# smartPowerStrip.net
KiCad netlist of a schematic drawn in EAGLE
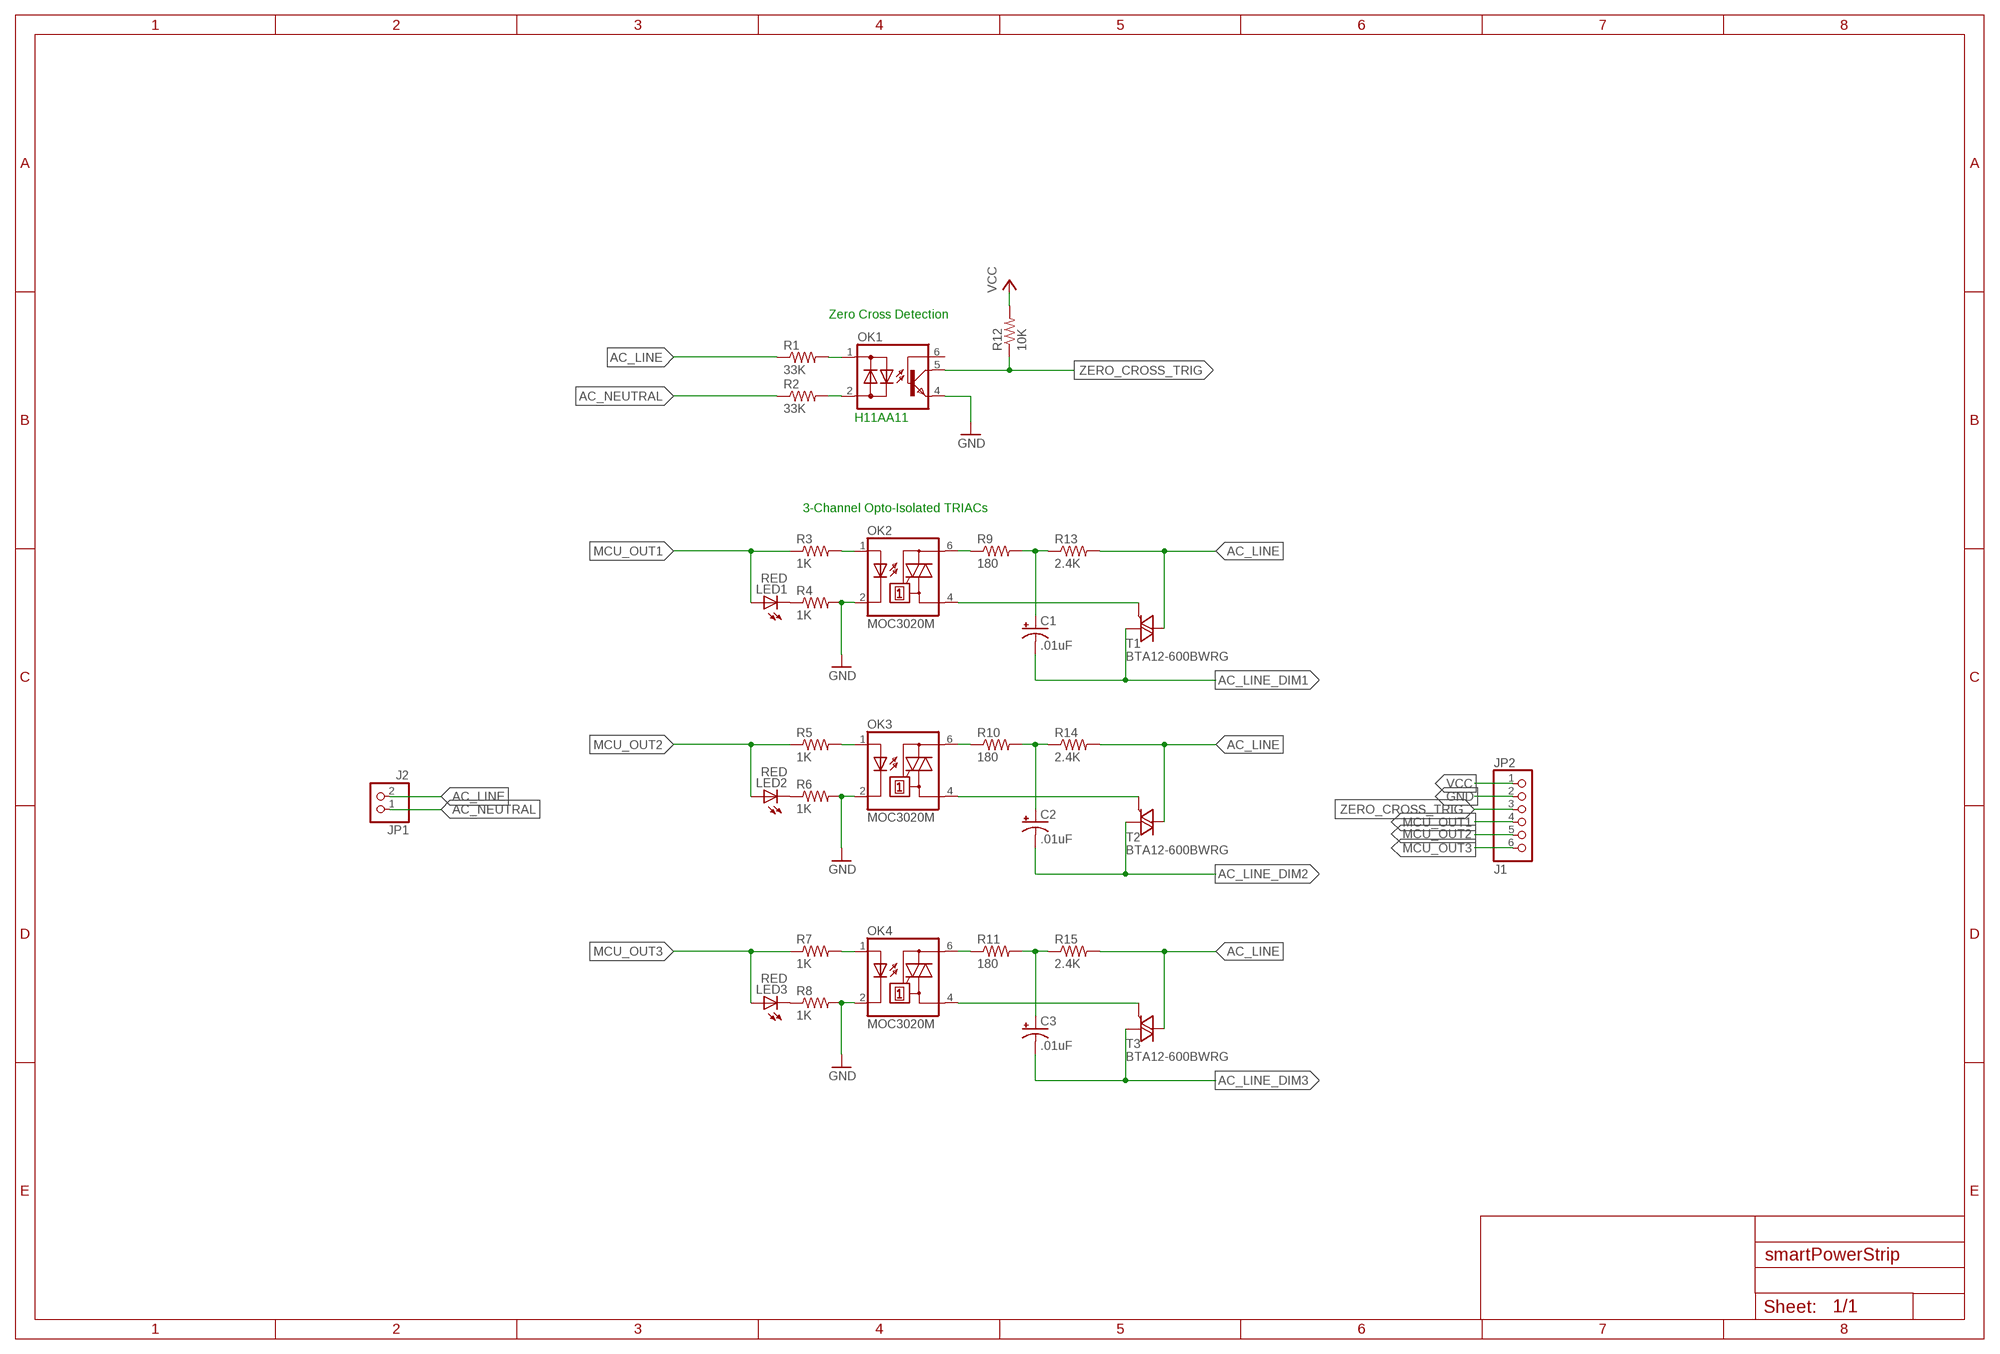
[diagram p0: schematic, sheet 1]

(export (version "E")
  (design (tool "Eeschema 10.0.6"))
  (components
    (comp (ref "C1")
      (value ".01uF")
      (footprint "eagle-import:TT2D5")
      (libsource (lib "eagle-import") (part "CPOL-USTT2D5"))
    )
    (comp (ref "C2")
      (value ".01uF")
      (footprint "eagle-import:TT2D5")
      (libsource (lib "eagle-import") (part "CPOL-USTT2D5"))
    )
    (comp (ref "C3")
      (value ".01uF")
      (footprint "eagle-import:TT2D5")
      (libsource (lib "eagle-import") (part "CPOL-USTT2D5"))
    )
    (comp (ref "JP1")
      (value "J2")
      (footprint "eagle-import:1X02")
      (libsource (lib "eagle-import") (part "PINHD-1X2"))
    )
    (comp (ref "JP2")
      (value "J1")
      (footprint "eagle-import:1X06")
      (libsource (lib "eagle-import") (part "PINHD-1X6"))
    )
    (comp (ref "LED1")
      (value "RED")
      (footprint "eagle-import:SFH480")
      (libsource (lib "eagle-import") (part "LEDSFH480"))
    )
    (comp (ref "LED2")
      (value "RED")
      (footprint "eagle-import:SFH480")
      (libsource (lib "eagle-import") (part "LEDSFH480"))
    )
    (comp (ref "LED3")
      (value "RED")
      (footprint "eagle-import:SFH480")
      (libsource (lib "eagle-import") (part "LEDSFH480"))
    )
    (comp (ref "OK1")
      (value "IL250")
      (footprint "eagle-import:DIL06")
      (fields (field (name "MF") "VISHAY/TELEFUNKEN"))
      (libsource (lib "eagle-import") (part "IL250"))
    )
    (comp (ref "OK2")
      (value "MOC3020M")
      (footprint "eagle-import:DIL06")
      (fields (field (name "MF") "FAIRCHILD SEMICONDUCTOR") (field (name "MPN") "MOC3020-M"))
      (libsource (lib "eagle-import") (part "MOC30M20"))
    )
    (comp (ref "OK3")
      (value "MOC3020M")
      (footprint "eagle-import:DIL06")
      (fields (field (name "MF") "FAIRCHILD SEMICONDUCTOR") (field (name "MPN") "MOC3020-M"))
      (libsource (lib "eagle-import") (part "MOC30M20"))
    )
    (comp (ref "OK4")
      (value "MOC3020M")
      (footprint "eagle-import:DIL06")
      (fields (field (name "MF") "FAIRCHILD SEMICONDUCTOR") (field (name "MPN") "MOC3020-M"))
      (libsource (lib "eagle-import") (part "MOC30M20"))
    )
    (comp (ref "R1")
      (value "33K")
      (footprint "eagle-import:0207_10")
      (libsource (lib "eagle-import") (part "R-US_0207/10"))
    )
    (comp (ref "R2")
      (value "33K")
      (footprint "eagle-import:0207_10")
      (libsource (lib "eagle-import") (part "R-US_0207/10"))
    )
    (comp (ref "R3")
      (value "1K")
      (footprint "eagle-import:0309V")
      (libsource (lib "eagle-import") (part "R-US_0309/V"))
    )
    (comp (ref "R4")
      (value "1K")
      (footprint "eagle-import:0309V")
      (libsource (lib "eagle-import") (part "R-US_0309/V"))
    )
    (comp (ref "R5")
      (value "1K")
      (footprint "eagle-import:0309V")
      (libsource (lib "eagle-import") (part "R-US_0309/V"))
    )
    (comp (ref "R6")
      (value "1K")
      (footprint "eagle-import:0309V")
      (libsource (lib "eagle-import") (part "R-US_0309/V"))
    )
    (comp (ref "R7")
      (value "1K")
      (footprint "eagle-import:0309V")
      (libsource (lib "eagle-import") (part "R-US_0309/V"))
    )
    (comp (ref "R8")
      (value "1K")
      (footprint "eagle-import:0309V")
      (libsource (lib "eagle-import") (part "R-US_0309/V"))
    )
    (comp (ref "R9")
      (value "180")
      (footprint "eagle-import:0309V")
      (libsource (lib "eagle-import") (part "R-US_0309/V"))
    )
    (comp (ref "R10")
      (value "180")
      (footprint "eagle-import:0309V")
      (libsource (lib "eagle-import") (part "R-US_0309/V"))
    )
    (comp (ref "R11")
      (value "180")
      (footprint "eagle-import:0309V")
      (libsource (lib "eagle-import") (part "R-US_0309/V"))
    )
    (comp (ref "R12")
      (value "10K")
      (footprint "eagle-import:0207_10")
      (libsource (lib "eagle-import") (part "R-US_0207/10"))
    )
    (comp (ref "R13")
      (value "2.4K")
      (footprint "eagle-import:0309V")
      (libsource (lib "eagle-import") (part "R-US_0309/V"))
    )
    (comp (ref "R14")
      (value "2.4K")
      (footprint "eagle-import:0309V")
      (libsource (lib "eagle-import") (part "R-US_0309/V"))
    )
    (comp (ref "R15")
      (value "2.4K")
      (footprint "eagle-import:0309V")
      (libsource (lib "eagle-import") (part "R-US_0309/V"))
    )
    (comp (ref "T1")
      (value "BTA12-600BWRG")
      (footprint "eagle-import:TO220BV")
      (libsource (lib "eagle-import") (part "BT138-V"))
    )
    (comp (ref "T2")
      (value "BTA12-600BWRG")
      (footprint "eagle-import:TO220BV")
      (libsource (lib "eagle-import") (part "BT138-V"))
    )
    (comp (ref "T3")
      (value "BTA12-600BWRG")
      (footprint "eagle-import:TO220BV")
      (libsource (lib "eagle-import") (part "BT138-V"))
    )
  )
  (nets
    (net (code "1") (name "AC_LINE") (class "Default")
      (node (ref "JP1") (pin "2") (pinfunction "2_2") (pintype "passive"))
      (node (ref "R1") (pin "1") (pinfunction "1_1") (pintype "passive"))
      (node (ref "R13") (pin "2") (pinfunction "2_2") (pintype "passive"))
      (node (ref "R14") (pin "2") (pinfunction "2_2") (pintype "passive"))
      (node (ref "R15") (pin "2") (pinfunction "2_2") (pintype "passive"))
      (node (ref "T1") (pin "T2") (pinfunction "A2_T2") (pintype "passive"))
      (node (ref "T2") (pin "T2") (pinfunction "A2_T2") (pintype "passive"))
      (node (ref "T3") (pin "T2") (pinfunction "A2_T2") (pintype "passive"))
    )
    (net (code "2") (name "AC_LINE_DIM1") (class "Default")
      (node (ref "C1") (pin "-") (pinfunction "-_-") (pintype "passive"))
      (node (ref "T1") (pin "T1") (pinfunction "A1_T1") (pintype "passive"))
    )
    (net (code "3") (name "AC_LINE_DIM2") (class "Default")
      (node (ref "C2") (pin "-") (pinfunction "-_-") (pintype "passive"))
      (node (ref "T2") (pin "T1") (pinfunction "A1_T1") (pintype "passive"))
    )
    (net (code "4") (name "AC_LINE_DIM3") (class "Default")
      (node (ref "C3") (pin "-") (pinfunction "-_-") (pintype "passive"))
      (node (ref "T3") (pin "T1") (pinfunction "A1_T1") (pintype "passive"))
    )
    (net (code "5") (name "AC_NEUTRAL") (class "Default")
      (node (ref "JP1") (pin "1") (pinfunction "1_1") (pintype "passive"))
      (node (ref "R2") (pin "1") (pinfunction "1_1") (pintype "passive"))
    )
    (net (code "6") (name "GND") (class "Default")
      (node (ref "JP2") (pin "2") (pinfunction "2_2") (pintype "passive"))
      (node (ref "OK1") (pin "4") (pinfunction "E_4") (pintype "passive"))
      (node (ref "OK2") (pin "2") (pinfunction "C_2") (pintype "passive"))
      (node (ref "OK3") (pin "2") (pinfunction "C_2") (pintype "passive"))
      (node (ref "OK4") (pin "2") (pinfunction "C_2") (pintype "passive"))
      (node (ref "R4") (pin "2") (pinfunction "2_2") (pintype "passive"))
      (node (ref "R6") (pin "2") (pinfunction "2_2") (pintype "passive"))
      (node (ref "R8") (pin "2") (pinfunction "2_2") (pintype "passive"))
    )
    (net (code "7") (name "MCU_OUT1") (class "Default")
      (node (ref "JP2") (pin "4") (pinfunction "4_4") (pintype "passive"))
      (node (ref "LED1") (pin "A") (pinfunction "A_A") (pintype "passive"))
      (node (ref "R3") (pin "1") (pinfunction "1_1") (pintype "passive"))
    )
    (net (code "8") (name "MCU_OUT2") (class "Default")
      (node (ref "JP2") (pin "5") (pinfunction "5_5") (pintype "passive"))
      (node (ref "LED2") (pin "A") (pinfunction "A_A") (pintype "passive"))
      (node (ref "R5") (pin "1") (pinfunction "1_1") (pintype "passive"))
    )
    (net (code "9") (name "MCU_OUT3") (class "Default")
      (node (ref "JP2") (pin "6") (pinfunction "6_6") (pintype "passive"))
      (node (ref "LED3") (pin "A") (pinfunction "A_A") (pintype "passive"))
      (node (ref "R7") (pin "1") (pinfunction "1_1") (pintype "passive"))
    )
    (net (code "10") (name "Net-(C1-Pad+)") (class "Default")
      (node (ref "C1") (pin "+") (pinfunction "+_+") (pintype "passive"))
      (node (ref "R13") (pin "1") (pinfunction "1_1") (pintype "passive"))
      (node (ref "R9") (pin "2") (pinfunction "2_2") (pintype "passive"))
    )
    (net (code "11") (name "Net-(C2-Pad+)") (class "Default")
      (node (ref "C2") (pin "+") (pinfunction "+_+") (pintype "passive"))
      (node (ref "R10") (pin "2") (pinfunction "2_2") (pintype "passive"))
      (node (ref "R14") (pin "1") (pinfunction "1_1") (pintype "passive"))
    )
    (net (code "12") (name "Net-(C3-Pad+)") (class "Default")
      (node (ref "C3") (pin "+") (pinfunction "+_+") (pintype "passive"))
      (node (ref "R11") (pin "2") (pinfunction "2_2") (pintype "passive"))
      (node (ref "R15") (pin "1") (pinfunction "1_1") (pintype "passive"))
    )
    (net (code "13") (name "Net-(LED1-C)") (class "Default")
      (node (ref "LED1") (pin "K") (pinfunction "C_K") (pintype "passive"))
      (node (ref "R4") (pin "1") (pinfunction "1_1") (pintype "passive"))
    )
    (net (code "14") (name "Net-(LED2-C)") (class "Default")
      (node (ref "LED2") (pin "K") (pinfunction "C_K") (pintype "passive"))
      (node (ref "R6") (pin "1") (pinfunction "1_1") (pintype "passive"))
    )
    (net (code "15") (name "Net-(LED3-C)") (class "Default")
      (node (ref "LED3") (pin "K") (pinfunction "C_K") (pintype "passive"))
      (node (ref "R8") (pin "1") (pinfunction "1_1") (pintype "passive"))
    )
    (net (code "16") (name "Net-(OK1-AC1)") (class "Default")
      (node (ref "OK1") (pin "1") (pinfunction "AC1_1") (pintype "passive"))
      (node (ref "R1") (pin "2") (pinfunction "2_2") (pintype "passive"))
    )
    (net (code "17") (name "Net-(OK1-AC2)") (class "Default")
      (node (ref "OK1") (pin "2") (pinfunction "AC2_2") (pintype "passive"))
      (node (ref "R2") (pin "2") (pinfunction "2_2") (pintype "passive"))
    )
    (net (code "18") (name "Net-(OK2-A)") (class "Default")
      (node (ref "OK2") (pin "1") (pinfunction "A_1") (pintype "passive"))
      (node (ref "R3") (pin "2") (pinfunction "2_2") (pintype "passive"))
    )
    (net (code "19") (name "Net-(OK2-A1)") (class "Default")
      (node (ref "OK2") (pin "4") (pinfunction "A1_4") (pintype "passive"))
      (node (ref "T1") (pin "G") (pinfunction "G_G") (pintype "passive"))
    )
    (net (code "20") (name "Net-(OK2-A2)") (class "Default")
      (node (ref "OK2") (pin "6") (pinfunction "A2_6") (pintype "passive"))
      (node (ref "R9") (pin "1") (pinfunction "1_1") (pintype "passive"))
    )
    (net (code "21") (name "Net-(OK3-A)") (class "Default")
      (node (ref "OK3") (pin "1") (pinfunction "A_1") (pintype "passive"))
      (node (ref "R5") (pin "2") (pinfunction "2_2") (pintype "passive"))
    )
    (net (code "22") (name "Net-(OK3-A1)") (class "Default")
      (node (ref "OK3") (pin "4") (pinfunction "A1_4") (pintype "passive"))
      (node (ref "T2") (pin "G") (pinfunction "G_G") (pintype "passive"))
    )
    (net (code "23") (name "Net-(OK3-A2)") (class "Default")
      (node (ref "OK3") (pin "6") (pinfunction "A2_6") (pintype "passive"))
      (node (ref "R10") (pin "1") (pinfunction "1_1") (pintype "passive"))
    )
    (net (code "24") (name "Net-(OK4-A)") (class "Default")
      (node (ref "OK4") (pin "1") (pinfunction "A_1") (pintype "passive"))
      (node (ref "R7") (pin "2") (pinfunction "2_2") (pintype "passive"))
    )
    (net (code "25") (name "Net-(OK4-A1)") (class "Default")
      (node (ref "OK4") (pin "4") (pinfunction "A1_4") (pintype "passive"))
      (node (ref "T3") (pin "G") (pinfunction "G_G") (pintype "passive"))
    )
    (net (code "26") (name "Net-(OK4-A2)") (class "Default")
      (node (ref "OK4") (pin "6") (pinfunction "A2_6") (pintype "passive"))
      (node (ref "R11") (pin "1") (pinfunction "1_1") (pintype "passive"))
    )
    (net (code "27") (name "VCC") (class "Default")
      (node (ref "JP2") (pin "1") (pinfunction "1_1") (pintype "passive"))
      (node (ref "R12") (pin "2") (pinfunction "2_2") (pintype "passive"))
    )
    (net (code "28") (name "ZERO_CROSS_TRIG") (class "Default")
      (node (ref "JP2") (pin "3") (pinfunction "3_3") (pintype "passive"))
      (node (ref "OK1") (pin "5") (pinfunction "C_5") (pintype "passive"))
      (node (ref "R12") (pin "1") (pinfunction "1_1") (pintype "passive"))
    )
    (net (code "29") (name "unconnected-(OK1-B-Pad6)") (class "Default")
      (node (ref "OK1") (pin "6") (pinfunction "B_6") (pintype "passive"))
    )
  )
)
